# USB_OTG_FS.net
KiCad netlist of a schematic drawn in Altium Designer
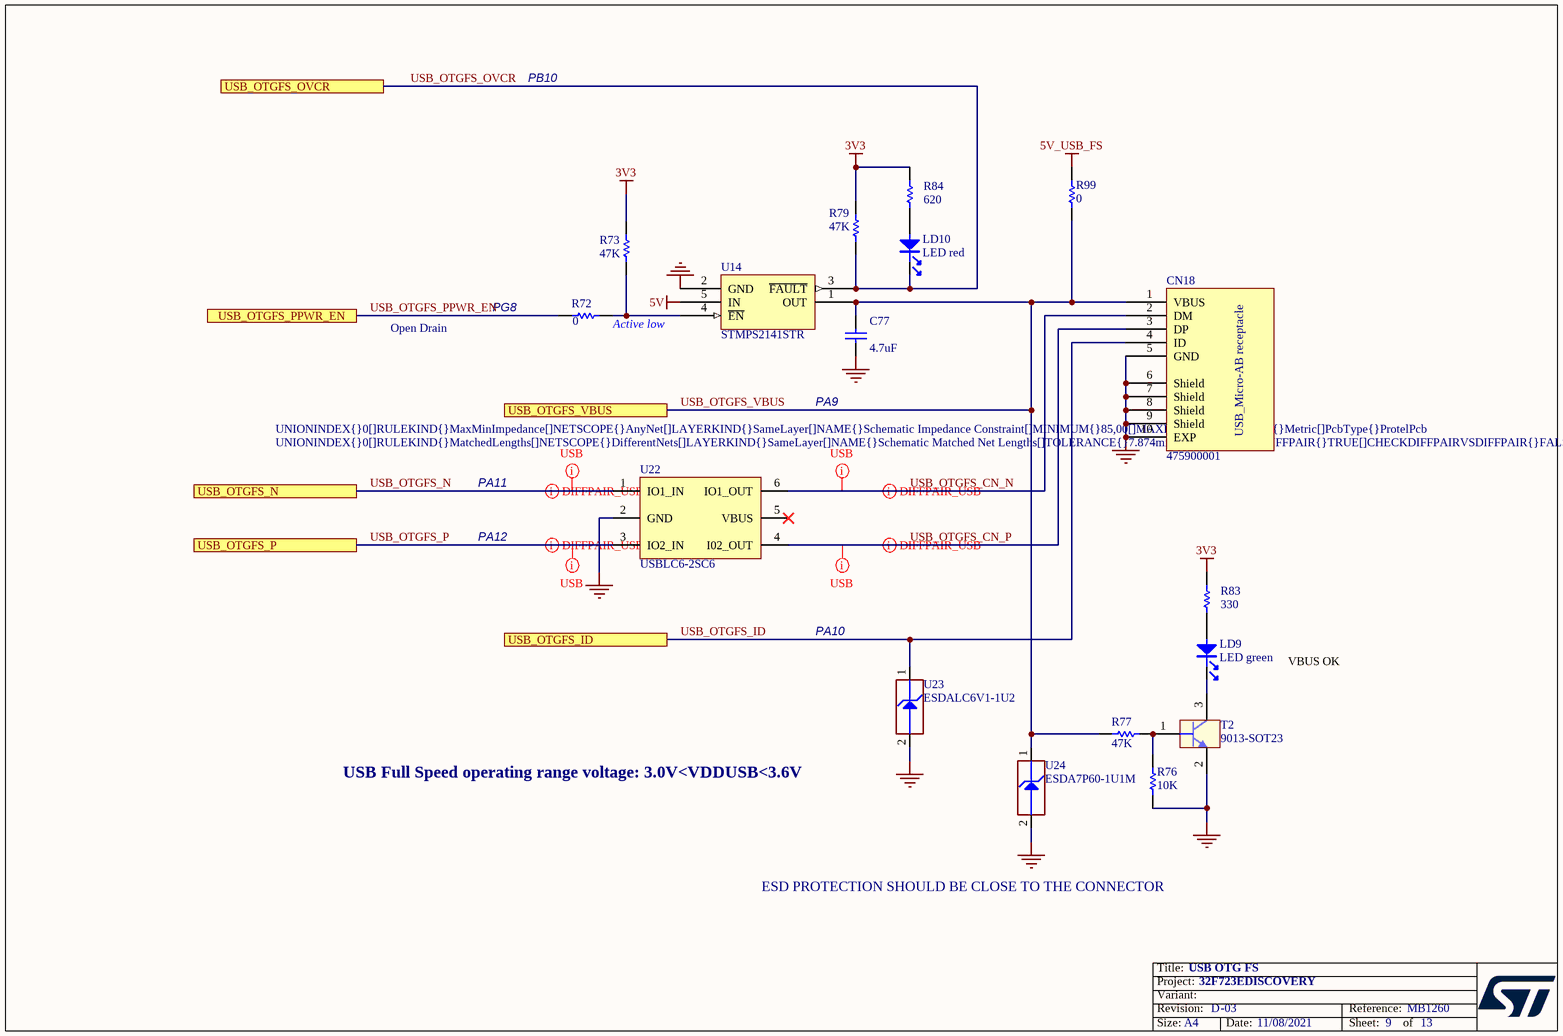
[diagram p0: USB_OTG_FS.SchDoc]

(export (version "E")
  (design (tool "Eeschema 10.0.6"))
  (components
    (comp (ref "C77")
      (value "4.7uF")
      (footprint "0603C")
      (description "Capacitor,4.7uF,16V, X5R,10%,0603,YAGEO")
      (libsource (lib "MCD_TOOLS") (part "Cap_4.7uF_X5R_10%_0603"))
    )
    (comp (ref "CN18")
      (value "475900001")
      (footprint "MOLEX_47590001")
      (description "USB-MICRO-AB, 47590-0001, SMT, MOLEX")
      (libsource (lib "MCD_TOOLS") (part "475900001"))
    )
    (comp (ref "LD9")
      (value "LED green")
      (footprint "0603D")
      (description "LED green 0603")
      (libsource (lib "MCD_TEMP_NPA") (part "LED_green"))
    )
    (comp (ref "LD10")
      (value "LED red")
      (footprint "0603D")
      (description "LED red 0603")
      (libsource (lib "MCD_TEMP_NPA") (part "LED_red"))
    )
    (comp (ref "R72")
      (value "0")
      (footprint "0603R-GS")
      (description "Resistor,0,0603,5%,YAGEO")
      (fields (field (name "Comment") "0_5%_0603"))
      (libsource (lib "MCD_TOOLS_RESISTOR") (part "Res_0_5%_0603"))
    )
    (comp (ref "R73")
      (value "47K")
      (footprint "0402R")
      (description "Resistor,47K,0402,1%,YAGEO")
      (fields (field (name "Comment") "47K_1%_0402"))
      (libsource (lib "MCD_TOOLS_RESISTOR") (part "Res_47K_1%_0402"))
    )
    (comp (ref "R76")
      (value "10K")
      (footprint "0402R")
      (description "Resistor,10K,0402,1%,YAGEO")
      (libsource (lib "MCD_TOOLS") (part "Res_10K_1%_0402"))
    )
    (comp (ref "R77")
      (value "47K")
      (footprint "0402R")
      (description "Resistor,47K,0402,1%,YAGEO")
      (fields (field (name "Comment") "47K_1%_0402"))
      (libsource (lib "MCD_TOOLS_RESISTOR") (part "Res_47K_1%_0402"))
    )
    (comp (ref "R79")
      (value "47K")
      (footprint "0402R")
      (description "Resistor,47K,0402,1%,YAGEO")
      (fields (field (name "Comment") "47K_1%_0402"))
      (libsource (lib "MCD_TOOLS_RESISTOR") (part "Res_47K_1%_0402"))
    )
    (comp (ref "R83")
      (value "330")
      (footprint "0603R")
      (description "Resistor,330,0603,1%,YAGEO")
      (fields (field (name "Comment") "330_1%_0603"))
      (libsource (lib "MCD_TOOLS_RESISTOR") (part "Res_330_1%_0603"))
    )
    (comp (ref "R84")
      (value "620")
      (footprint "0603R")
      (description "Resistor,620,0603,1%,VISHAY")
      (fields (field (name "Comment") "620_1%_0603"))
      (libsource (lib "MCD_TOOLS_RESISTOR") (part "Res_620_1%_0603"))
    )
    (comp (ref "R99")
      (value "0")
      (footprint "0603R-GS")
      (description "Resistor,0,0603,5%,YAGEO")
      (fields (field (name "Comment") "0_5%_0603"))
      (libsource (lib "MCD_TOOLS_RESISTOR") (part "Res_0_5%_0603"))
    )
    (comp (ref "T2")
      (value "9013-SOT23")
      (footprint "SOT-23")
      (description "NPN Bipolar Transistor")
      (libsource (lib "MCD_TOOLS_MISCELLANEOUS") (part "9013-SOT23"))
    )
    (comp (ref "U14")
      (value "STMPS2141STR")
      (footprint "SOT23-5")
      (description "Enhanced single channel power switches")
      (libsource (lib "MCD_TEMP_NPA") (part "STMPS2141STR"))
    )
    (comp (ref "U22")
      (value "USBLC6-2SC6")
      (footprint "SOT23-6")
      (description "Very low capacitance ESD protection")
      (libsource (lib "MCD_TEMP_NPA") (part "USBLC6-2SC6"))
    )
    (comp (ref "U23")
      (value "ESDALC6V1-1U2")
      (footprint "ESD_ST0201")
      (description "Dual Transil array for ESD protection")
      (libsource (lib "MCD_TEMP_PCH") (part "ESDALC6V1-1U2"))
    )
    (comp (ref "U24")
      (value "ESDA7P60-1U1M")
      (footprint "ESD_ST0201")
      (description "High power transient voltage suppressor, 7V breakdown")
      (fields (field (name "INTERNAL_PART_NUMBER") "MCD-00251") (field (name "PROVIDED_BY") "STM"))
      (libsource (lib "MCD_PARTS_database") (part "ESDA7P60-1U1M"))
    )
  )
  (nets
    (net (code "1") (name "/USB_OTGFS_CN_N") (class "Default")
      (node (ref "CN18") (pin "2") (pinfunction "DM_2") (pintype "passive"))
      (node (ref "U22") (pin "6") (pinfunction "IO1_OUT_6") (pintype "passive"))
    )
    (net (code "2") (name "/USB_OTGFS_CN_P") (class "Default")
      (node (ref "CN18") (pin "3") (pinfunction "DP_3") (pintype "passive"))
      (node (ref "U22") (pin "4") (pinfunction "I02_OUT_4") (pintype "passive"))
    )
    (net (code "3") (name "/USB_OTGFS_ID") (class "Default")
      (node (ref "CN18") (pin "4") (pinfunction "ID_4") (pintype "passive"))
      (node (ref "U23") (pin "1") (pinfunction "IO1_1") (pintype "passive"))
    )
    (net (code "4") (name "/USB_OTGFS_N") (class "Default")
      (node (ref "U22") (pin "1") (pinfunction "IO1_IN_1") (pintype "passive"))
    )
    (net (code "5") (name "/USB_OTGFS_OVCR") (class "Default")
      (node (ref "LD10") (pin "2") (pintype "passive"))
      (node (ref "R79") (pin "1") (pinfunction "1_1") (pintype "passive"))
      (node (ref "U14") (pin "3") (pinfunction "~{FAULT}_3") (pintype "output"))
    )
    (net (code "6") (name "/USB_OTGFS_P") (class "Default")
      (node (ref "U22") (pin "3") (pinfunction "IO2_IN_3") (pintype "passive"))
    )
    (net (code "7") (name "/USB_OTGFS_PPWR_EN") (class "Default")
      (node (ref "R72") (pin "1") (pinfunction "1_1") (pintype "passive"))
    )
    (net (code "8") (name "/USB_OTGFS_VBUS") (class "Default")
      (node (ref "C77") (pin "1") (pinfunction "1_1") (pintype "passive"))
      (node (ref "CN18") (pin "1") (pinfunction "VBUS_1") (pintype "passive"))
      (node (ref "R77") (pin "2") (pinfunction "2_2") (pintype "passive"))
      (node (ref "R99") (pin "1") (pinfunction "1_1") (pintype "passive"))
      (node (ref "U14") (pin "1") (pinfunction "OUT_1") (pintype "passive"))
      (node (ref "U24") (pin "1") (pinfunction "IO1_1") (pintype "passive"))
    )
    (net (code "9") (name "3V3") (class "Default")
      (node (ref "R73") (pin "2") (pinfunction "2_2") (pintype "passive"))
      (node (ref "R79") (pin "2") (pinfunction "2_2") (pintype "passive"))
      (node (ref "R83") (pin "2") (pinfunction "2_2") (pintype "passive"))
      (node (ref "R84") (pin "2") (pinfunction "2_2") (pintype "passive"))
    )
    (net (code "10") (name "5V") (class "Default")
      (node (ref "U14") (pin "5") (pinfunction "IN_5") (pintype "passive"))
    )
    (net (code "11") (name "5V_USB_FS") (class "Default")
      (node (ref "R99") (pin "2") (pinfunction "2_2") (pintype "passive"))
    )
    (net (code "12") (name "GND") (class "Default")
      (node (ref "C77") (pin "2") (pinfunction "2_2") (pintype "passive"))
      (node (ref "CN18") (pin "10") (pinfunction "EXP_10") (pintype "passive"))
      (node (ref "CN18") (pin "5") (pinfunction "GND_5") (pintype "passive"))
      (node (ref "CN18") (pin "6") (pinfunction "Shield_6") (pintype "passive"))
      (node (ref "CN18") (pin "7") (pinfunction "Shield_7") (pintype "passive"))
      (node (ref "CN18") (pin "8") (pinfunction "Shield_8") (pintype "passive"))
      (node (ref "CN18") (pin "9") (pinfunction "Shield_9") (pintype "passive"))
      (node (ref "R76") (pin "1") (pinfunction "1_1") (pintype "passive"))
      (node (ref "T2") (pin "2") (pinfunction "E_2") (pintype "passive"))
      (node (ref "U14") (pin "2") (pinfunction "GND_2") (pintype "passive"))
      (node (ref "U22") (pin "2") (pinfunction "GND_2") (pintype "passive"))
      (node (ref "U23") (pin "2") (pinfunction "GND_2") (pintype "passive"))
      (node (ref "U24") (pin "2") (pinfunction "GND_2") (pintype "passive"))
    )
    (net (code "13") (name "Net-(LD9-Pad1)") (class "Default")
      (node (ref "LD9") (pin "1") (pintype "passive"))
      (node (ref "R83") (pin "1") (pinfunction "1_1") (pintype "passive"))
    )
    (net (code "14") (name "Net-(LD10-Pad1)") (class "Default")
      (node (ref "LD10") (pin "1") (pintype "passive"))
      (node (ref "R84") (pin "1") (pinfunction "1_1") (pintype "passive"))
    )
    (net (code "15") (name "Net-(T2-B)") (class "Default")
      (node (ref "R76") (pin "2") (pinfunction "2_2") (pintype "passive"))
      (node (ref "R77") (pin "1") (pinfunction "1_1") (pintype "passive"))
      (node (ref "T2") (pin "1") (pinfunction "B_1") (pintype "passive"))
    )
    (net (code "16") (name "Net-(T2-C)") (class "Default")
      (node (ref "LD9") (pin "2") (pintype "passive"))
      (node (ref "T2") (pin "3") (pinfunction "C_3") (pintype "passive"))
    )
    (net (code "17") (name "Net-(U14-~{EN})") (class "Default")
      (node (ref "R72") (pin "2") (pinfunction "2_2") (pintype "passive"))
      (node (ref "R73") (pin "1") (pinfunction "1_1") (pintype "passive"))
      (node (ref "U14") (pin "4") (pinfunction "~{EN}_4") (pintype "input"))
    )
    (net (code "18") (name "unconnected-(U22-VBUS-Pad5)") (class "Default")
      (node (ref "U22") (pin "5") (pinfunction "VBUS_5") (pintype "passive+no_connect"))
    )
  )
)
